# MCU2.net
KiCad netlist of a schematic drawn in Altium Designer
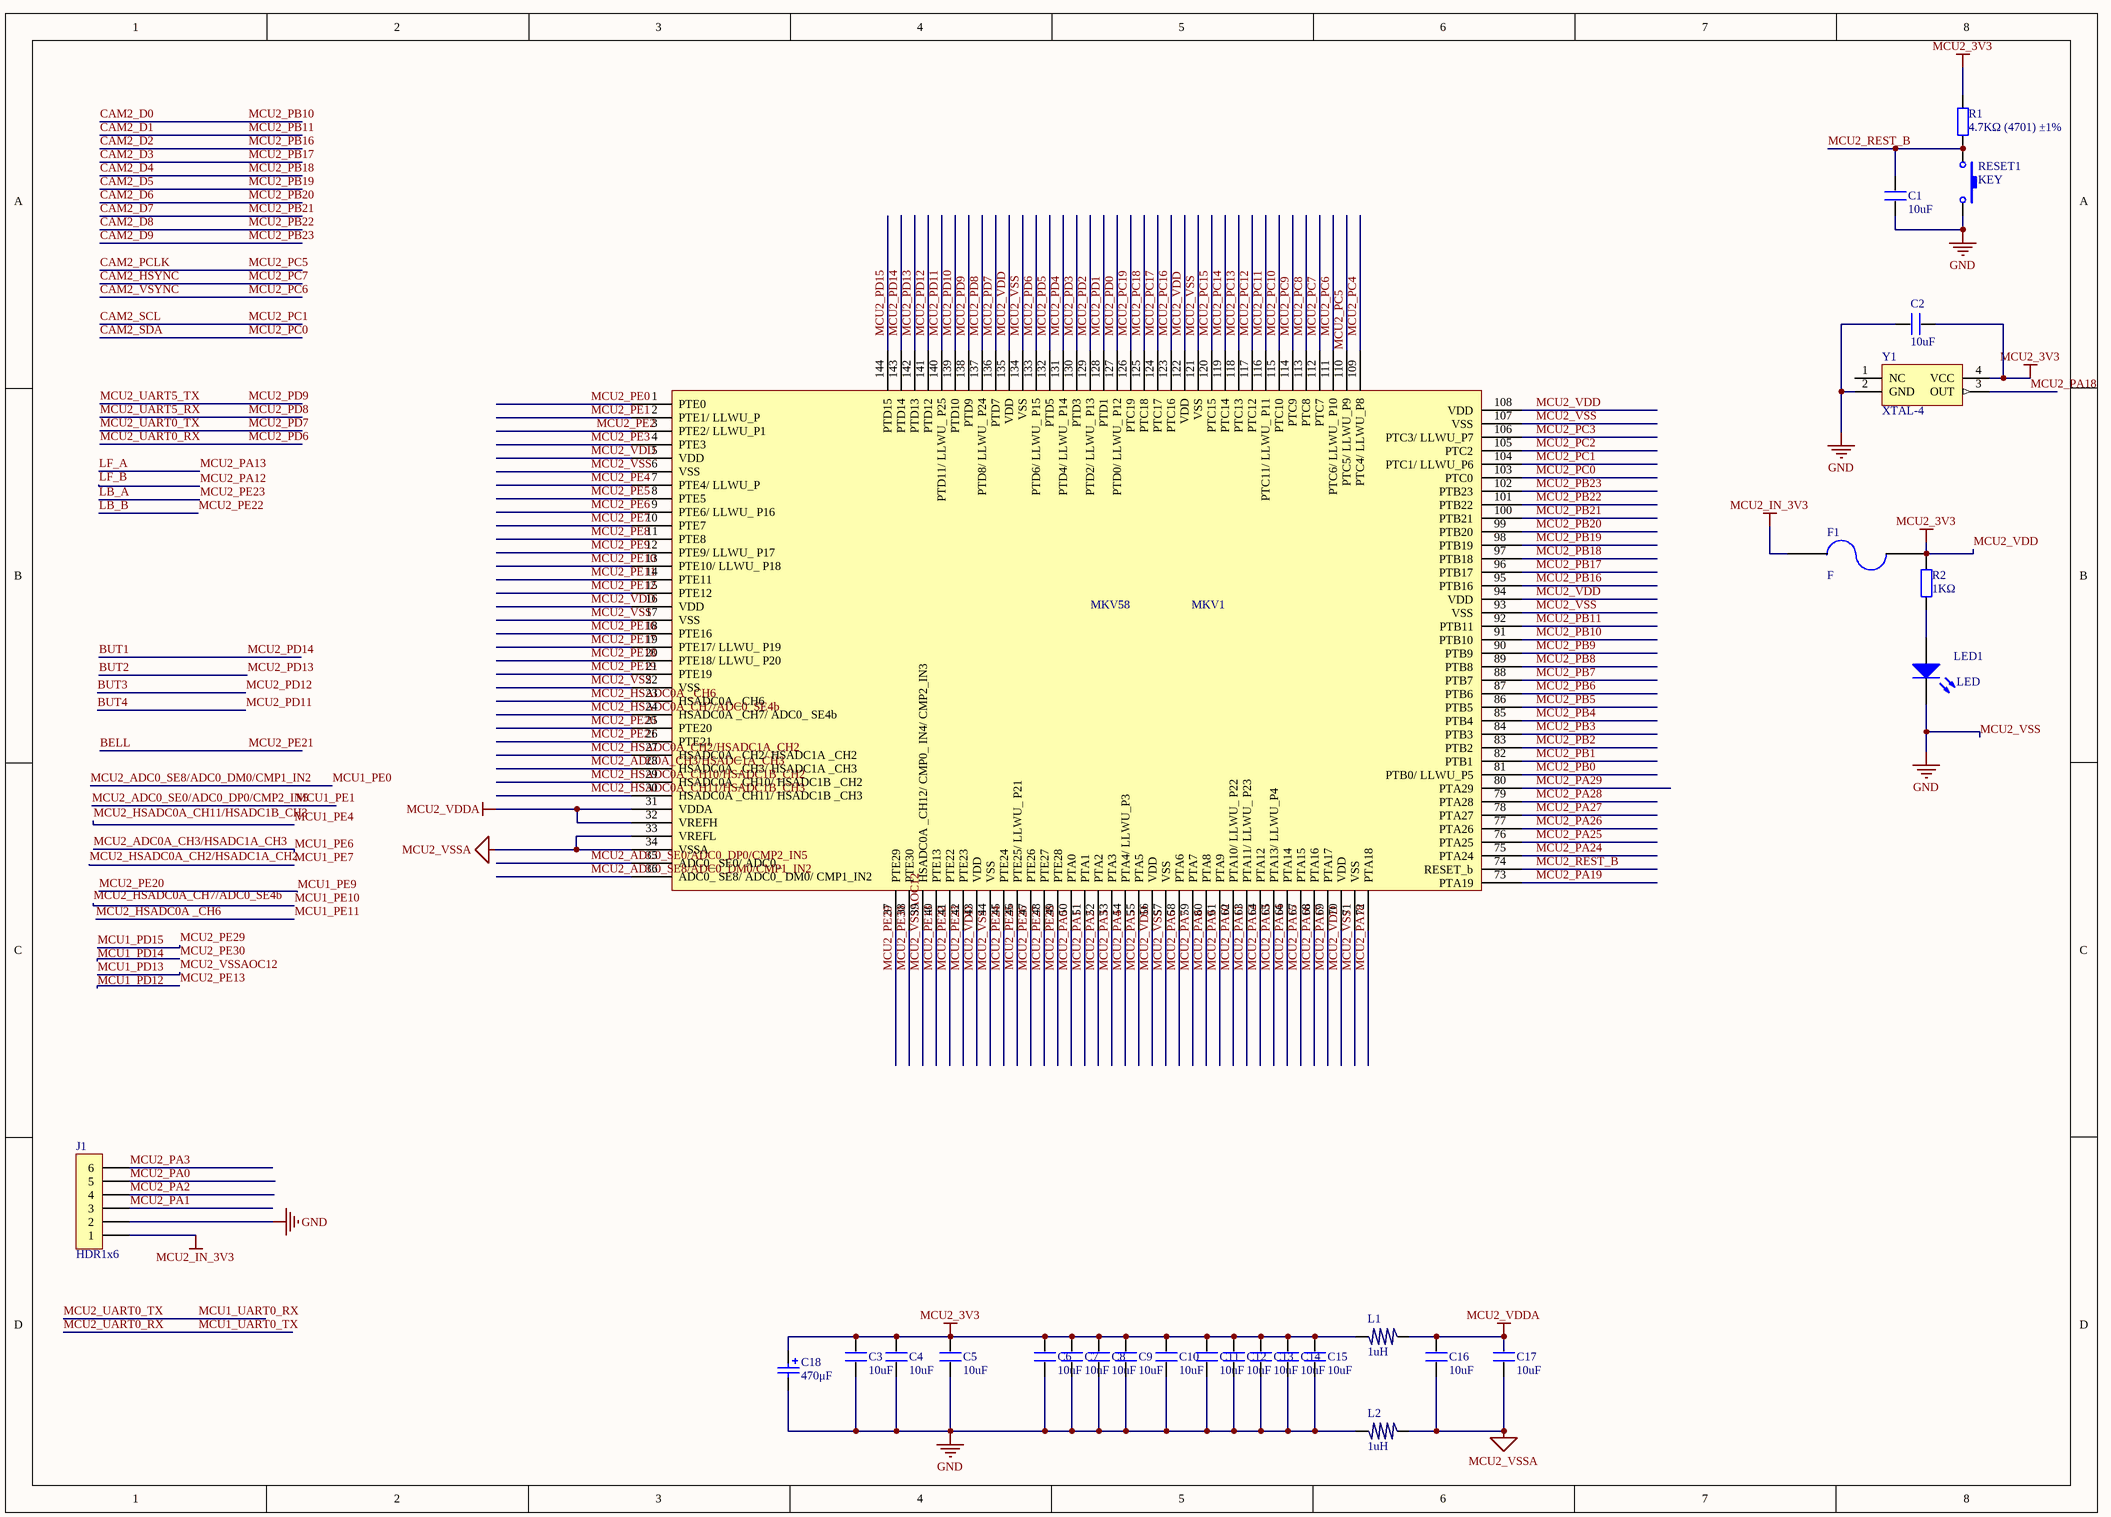
[diagram p0: MCU2.SchDoc]

(export (version "E")
  (design (tool "Eeschema 10.0.6"))
  (components
    (comp (ref "C1") (value "10uF") (footprint "0805_C") (libsource (lib "MyLib") (part "C")))
    (comp (ref "C2") (value "10uF") (footprint "0805_C") (libsource (lib "MyLib") (part "C")))
    (comp (ref "C3") (value "10uF") (footprint "0805_C") (libsource (lib "MyLib") (part "C")))
    (comp (ref "C4") (value "10uF") (footprint "0805_C") (libsource (lib "MyLib") (part "C")))
    (comp (ref "C5") (value "10uF") (footprint "0805_C") (libsource (lib "MyLib") (part "C")))
    (comp (ref "C6") (value "10uF") (footprint "0805_C") (libsource (lib "MyLib") (part "C")))
    (comp (ref "C7") (value "10uF") (footprint "0805_C") (libsource (lib "MyLib") (part "C")))
    (comp (ref "C8") (value "10uF") (footprint "0805_C") (libsource (lib "MyLib") (part "C")))
    (comp (ref "C9") (value "10uF") (footprint "0805_C") (libsource (lib "MyLib") (part "C")))
    (comp (ref "C10") (value "10uF") (footprint "0805_C") (libsource (lib "MyLib") (part "C")))
    (comp (ref "C11") (value "10uF") (footprint "0805_C") (libsource (lib "MyLib") (part "C")))
    (comp (ref "C12") (value "10uF") (footprint "0805_C") (libsource (lib "MyLib") (part "C")))
    (comp (ref "C13") (value "10uF") (footprint "0805_C") (libsource (lib "MyLib") (part "C")))
    (comp (ref "C14") (value "10uF") (footprint "0805_C") (libsource (lib "MyLib") (part "C")))
    (comp (ref "C15") (value "10uF") (footprint "0805_C") (libsource (lib "MyLib") (part "C")))
    (comp (ref "C16") (value "10uF") (footprint "0805_C") (libsource (lib "MyLib") (part "C")))
    (comp (ref "C17") (value "10uF") (footprint "0805_C") (libsource (lib "MyLib") (part "C")))
    (comp (ref "C18")
      (value "470μF")
      (footprint "CASE C6032")
      (fields (field (name "ALTIUM_UNNAMED_1") "470μF"))
      (libsource (lib "MyLib") (part "Cap(Ta)"))
    )
    (comp (ref "F1") (value "F") (footprint "0805_R") (libsource (lib "MKV58") (part "F")))
    (comp (ref "J1")
      (value "HDR1x6")
      (footprint "PIN-6-2.54-1.0")
      (description "Connector")
      (libsource (lib "MyLib") (part "HDR1x6"))
    )
    (comp (ref "L1") (value "1uH") (footprint "0805") (libsource (lib "MyLib") (part "L")))
    (comp (ref "L2") (value "1uH") (footprint "0805") (libsource (lib "MyLib") (part "L")))
    (comp (ref "LED1") (value "LED") (footprint "LED(0805)") (libsource (lib "MyLib") (part "LED(0805)")))
    (comp (ref "MKV1") (value "MKV58") (footprint "LQFP144") (libsource (lib "MyLib") (part "MKV58")))
    (comp (ref "R1")
      (value "4.7KΩ (4701) ±1%")
      (footprint "0805_R")
      (description "贴片电阻")
      (libsource (lib "MyLib") (part "0805 4.7KΩ (4701) 1%"))
    )
    (comp (ref "R2")
      (value "1KΩ")
      (footprint "0805_R")
      (description "贴片电阻")
      (libsource (lib "MyLib") (part "0805 1.5KΩ (1501) 1%"))
    )
    (comp (ref "RESET1") (value "KEY") (footprint "Key_PB") (libsource (lib "MyLib") (part "Key_1")))
    (comp (ref "Y1")
      (value "XTAL-4")
      (footprint "XTAL-5.0X3.2")
      (description "Oscillator")
      (libsource (lib "MyLib") (part "XTAL-4"))
    )
  )
  (nets
    (net (code "2") (name "/BELL") (class "Default")
      (node (ref "MKV1") (pin "26") (pinfunction "PTE21_26") (pintype "passive"))
    )
    (net (code "3") (name "/BUT1") (class "Default")
      (node (ref "MKV1") (pin "143") (pinfunction "PTD14_143") (pintype "passive"))
    )
    (net (code "4") (name "/BUT2") (class "Default")
      (node (ref "MKV1") (pin "142") (pinfunction "PTD13_142") (pintype "passive"))
    )
    (net (code "5") (name "/BUT3") (class "Default")
      (node (ref "MKV1") (pin "141") (pinfunction "PTD12_141") (pintype "passive"))
    )
    (net (code "6") (name "/BUT4") (class "Default")
      (node (ref "MKV1") (pin "140") (pinfunction "PTD11/_LLWU__P25_140") (pintype "passive"))
    )
    (net (code "7") (name "/CAM2_D0") (class "Default")
      (node (ref "MKV1") (pin "91") (pinfunction "PTB10_91") (pintype "passive"))
    )
    (net (code "8") (name "/CAM2_D1") (class "Default")
      (node (ref "MKV1") (pin "92") (pinfunction "PTB11_92") (pintype "passive"))
    )
    (net (code "9") (name "/CAM2_D2") (class "Default")
      (node (ref "MKV1") (pin "95") (pinfunction "PTB16_95") (pintype "passive"))
    )
    (net (code "10") (name "/CAM2_D3") (class "Default")
      (node (ref "MKV1") (pin "96") (pinfunction "PTB17_96") (pintype "passive"))
    )
    (net (code "11") (name "/CAM2_D4") (class "Default")
      (node (ref "MKV1") (pin "97") (pinfunction "PTB18_97") (pintype "passive"))
    )
    (net (code "12") (name "/CAM2_D5") (class "Default")
      (node (ref "MKV1") (pin "98") (pinfunction "PTB19_98") (pintype "passive"))
    )
    (net (code "13") (name "/CAM2_D6") (class "Default")
      (node (ref "MKV1") (pin "99") (pinfunction "PTB20_99") (pintype "passive"))
    )
    (net (code "14") (name "/CAM2_D7") (class "Default")
      (node (ref "MKV1") (pin "100") (pinfunction "PTB21_100") (pintype "passive"))
    )
    (net (code "15") (name "/CAM2_D8") (class "Default")
      (node (ref "MKV1") (pin "101") (pinfunction "PTB22_101") (pintype "passive"))
    )
    (net (code "16") (name "/CAM2_D9") (class "Default")
      (node (ref "MKV1") (pin "102") (pinfunction "PTB23_102") (pintype "passive"))
    )
    (net (code "17") (name "/CAM2_HSYNC") (class "Default")
      (node (ref "MKV1") (pin "112") (pinfunction "PTC7_112") (pintype "passive"))
    )
    (net (code "18") (name "/CAM2_PCLK") (class "Default")
      (node (ref "MKV1") (pin "110") (pinfunction "PTC5/_LLWU_P9_110") (pintype "passive"))
    )
    (net (code "19") (name "/CAM2_SCL") (class "Default")
      (node (ref "MKV1") (pin "104") (pinfunction "PTC1/_LLWU_P6_104") (pintype "passive"))
    )
    (net (code "20") (name "/CAM2_SDA") (class "Default")
      (node (ref "MKV1") (pin "103") (pinfunction "PTC0_103") (pintype "passive"))
    )
    (net (code "21") (name "/CAM2_VSYNC") (class "Default")
      (node (ref "MKV1") (pin "111") (pinfunction "PTC6/_LLWU__P10_111") (pintype "passive"))
    )
    (net (code "22") (name "/LB_A") (class "Default")
      (node (ref "MKV1") (pin "42") (pinfunction "PTE23_42") (pintype "passive"))
    )
    (net (code "23") (name "/LB_B") (class "Default")
      (node (ref "MKV1") (pin "41") (pinfunction "PTE22_41") (pintype "passive"))
    )
    (net (code "24") (name "/LF_A") (class "Default")
      (node (ref "MKV1") (pin "65") (pinfunction "PTA13/_LLWU_P4_65") (pintype "passive"))
    )
    (net (code "25") (name "/LF_B") (class "Default")
      (node (ref "MKV1") (pin "64") (pinfunction "PTA12_64") (pintype "passive"))
    )
    (net (code "26") (name "/MCU1_PD12") (class "Default")
      (node (ref "MKV1") (pin "40") (pinfunction "PTE13_40") (pintype "passive"))
    )
    (net (code "27") (name "/MCU1_PD13") (class "Default")
      (node (ref "MKV1") (pin "39") (pinfunction "HSADC0A__CH12/_CMP0__IN4/_CMP2_IN3_39") (pintype "passive"))
    )
    (net (code "28") (name "/MCU1_PD14") (class "Default")
      (node (ref "MKV1") (pin "38") (pinfunction "PTE30_38") (pintype "passive"))
    )
    (net (code "29") (name "/MCU1_PD15") (class "Default")
      (node (ref "MKV1") (pin "37") (pinfunction "PTE29_37") (pintype "passive"))
    )
    (net (code "30") (name "/MCU1_PE0") (class "Default")
      (node (ref "MKV1") (pin "36") (pinfunction "ADC0__SE8/_ADC0__DM0/_CMP1_IN2_36") (pintype "passive"))
    )
    (net (code "31") (name "/MCU1_PE1") (class "Default")
      (node (ref "MKV1") (pin "35") (pinfunction "ADC0__SE0/_ADC0__35") (pintype "passive"))
    )
    (net (code "32") (name "/MCU1_PE4") (class "Default")
      (node (ref "MKV1") (pin "30") (pinfunction "HSADC0A__CH11/_HSADC1B__CH3_30") (pintype "passive"))
    )
    (net (code "33") (name "/MCU1_PE6") (class "Default")
      (node (ref "MKV1") (pin "28") (pinfunction "HSADC0A__CH3/_HSADC1A__CH3_28") (pintype "passive"))
    )
    (net (code "34") (name "/MCU1_PE7") (class "Default")
      (node (ref "MKV1") (pin "27") (pinfunction "HSADC0A__CH2/_HSADC1A__CH2_27") (pintype "passive"))
    )
    (net (code "35") (name "/MCU1_PE9") (class "Default")
      (node (ref "MKV1") (pin "25") (pinfunction "PTE20_25") (pintype "passive"))
    )
    (net (code "36") (name "/MCU1_PE10") (class "Default")
      (node (ref "MKV1") (pin "24") (pinfunction "HSADC0A__CH7/_ADC0__SE4b_24") (pintype "passive"))
    )
    (net (code "37") (name "/MCU1_PE11") (class "Default")
      (node (ref "MKV1") (pin "23") (pinfunction "HSADC0A__CH6_23") (pintype "passive"))
    )
    (net (code "38") (name "/MCU1_UART0_RX") (class "Default")
      (node (ref "MKV1") (pin "136") (pinfunction "PTD7_136") (pintype "passive"))
    )
    (net (code "39") (name "/MCU1_UART0_TX") (class "Default")
      (node (ref "MKV1") (pin "133") (pinfunction "PTD6/_LLWU__P15_133") (pintype "passive"))
    )
    (net (code "40") (name "/MCU2_HSADC0A_CH10{slash}HSADC1B_CH2") (class "Default")
      (node (ref "MKV1") (pin "29") (pinfunction "HSADC0A__CH10/_HSADC1B__CH2_29") (pintype "passive"))
    )
    (net (code "41") (name "/MCU2_PA0") (class "Default")
      (node (ref "J1") (pin "5") (pinfunction "5_5") (pintype "passive"))
      (node (ref "MKV1") (pin "50") (pinfunction "PTA0_50") (pintype "passive"))
    )
    (net (code "42") (name "/MCU2_PA1") (class "Default")
      (node (ref "J1") (pin "3") (pinfunction "3_3") (pintype "passive"))
      (node (ref "MKV1") (pin "51") (pinfunction "PTA1_51") (pintype "passive"))
    )
    (net (code "43") (name "/MCU2_PA2") (class "Default")
      (node (ref "J1") (pin "4") (pinfunction "4_4") (pintype "passive"))
      (node (ref "MKV1") (pin "52") (pinfunction "PTA2_52") (pintype "passive"))
    )
    (net (code "44") (name "/MCU2_PA3") (class "Default")
      (node (ref "J1") (pin "6") (pinfunction "6_6") (pintype "passive"))
      (node (ref "MKV1") (pin "53") (pinfunction "PTA3_53") (pintype "passive"))
    )
    (net (code "45") (name "/MCU2_PA4") (class "Default")
      (node (ref "MKV1") (pin "54") (pinfunction "PTA4/_LLWU_P3_54") (pintype "passive"))
    )
    (net (code "46") (name "/MCU2_PA5") (class "Default")
      (node (ref "MKV1") (pin "55") (pinfunction "PTA5_55") (pintype "passive"))
    )
    (net (code "47") (name "/MCU2_PA6") (class "Default")
      (node (ref "MKV1") (pin "58") (pinfunction "PTA6_58") (pintype "passive"))
    )
    (net (code "48") (name "/MCU2_PA7") (class "Default")
      (node (ref "MKV1") (pin "59") (pinfunction "PTA7_59") (pintype "passive"))
    )
    (net (code "49") (name "/MCU2_PA8") (class "Default")
      (node (ref "MKV1") (pin "60") (pinfunction "PTA8_60") (pintype "passive"))
    )
    (net (code "50") (name "/MCU2_PA9") (class "Default")
      (node (ref "MKV1") (pin "61") (pinfunction "PTA9_61") (pintype "passive"))
    )
    (net (code "51") (name "/MCU2_PA10") (class "Default")
      (node (ref "MKV1") (pin "62") (pinfunction "PTA10/_LLWU__P22_62") (pintype "passive"))
    )
    (net (code "52") (name "/MCU2_PA11") (class "Default")
      (node (ref "MKV1") (pin "63") (pinfunction "PTA11/_LLWU__P23_63") (pintype "passive"))
    )
    (net (code "53") (name "/MCU2_PA14") (class "Default")
      (node (ref "MKV1") (pin "66") (pinfunction "PTA14_66") (pintype "passive"))
    )
    (net (code "54") (name "/MCU2_PA15") (class "Default")
      (node (ref "MKV1") (pin "67") (pinfunction "PTA15_67") (pintype "passive"))
    )
    (net (code "55") (name "/MCU2_PA16") (class "Default")
      (node (ref "MKV1") (pin "68") (pinfunction "PTA16_68") (pintype "passive"))
    )
    (net (code "56") (name "/MCU2_PA17") (class "Default")
      (node (ref "MKV1") (pin "69") (pinfunction "PTA17_69") (pintype "passive"))
    )
    (net (code "57") (name "/MCU2_PA18") (class "Default")
      (node (ref "MKV1") (pin "72") (pinfunction "PTA18_72") (pintype "passive"))
      (node (ref "Y1") (pin "3") (pinfunction "OUT_3") (pintype "output"))
    )
    (net (code "58") (name "/MCU2_PA19") (class "Default")
      (node (ref "MKV1") (pin "73") (pinfunction "PTA19_73") (pintype "passive"))
    )
    (net (code "59") (name "/MCU2_PA24") (class "Default")
      (node (ref "MKV1") (pin "75") (pinfunction "PTA24_75") (pintype "passive"))
    )
    (net (code "60") (name "/MCU2_PA25") (class "Default")
      (node (ref "MKV1") (pin "76") (pinfunction "PTA25_76") (pintype "passive"))
    )
    (net (code "61") (name "/MCU2_PA26") (class "Default")
      (node (ref "MKV1") (pin "77") (pinfunction "PTA26_77") (pintype "passive"))
    )
    (net (code "62") (name "/MCU2_PA27") (class "Default")
      (node (ref "MKV1") (pin "78") (pinfunction "PTA27_78") (pintype "passive"))
    )
    (net (code "63") (name "/MCU2_PA28") (class "Default")
      (node (ref "MKV1") (pin "79") (pinfunction "PTA28_79") (pintype "passive"))
    )
    (net (code "64") (name "/MCU2_PA29") (class "Default")
      (node (ref "MKV1") (pin "80") (pinfunction "PTA29_80") (pintype "passive"))
    )
    (net (code "65") (name "/MCU2_PB0") (class "Default")
      (node (ref "MKV1") (pin "81") (pinfunction "PTB0/_LLWU_P5_81") (pintype "passive"))
    )
    (net (code "66") (name "/MCU2_PB1") (class "Default")
      (node (ref "MKV1") (pin "82") (pinfunction "PTB1_82") (pintype "passive"))
    )
    (net (code "67") (name "/MCU2_PB2") (class "Default")
      (node (ref "MKV1") (pin "83") (pinfunction "PTB2_83") (pintype "passive"))
    )
    (net (code "68") (name "/MCU2_PB3") (class "Default")
      (node (ref "MKV1") (pin "84") (pinfunction "PTB3_84") (pintype "passive"))
    )
    (net (code "69") (name "/MCU2_PB4") (class "Default")
      (node (ref "MKV1") (pin "85") (pinfunction "PTB4_85") (pintype "passive"))
    )
    (net (code "70") (name "/MCU2_PB5") (class "Default")
      (node (ref "MKV1") (pin "86") (pinfunction "PTB5_86") (pintype "passive"))
    )
    (net (code "71") (name "/MCU2_PB6") (class "Default")
      (node (ref "MKV1") (pin "87") (pinfunction "PTB6_87") (pintype "passive"))
    )
    (net (code "72") (name "/MCU2_PB7") (class "Default")
      (node (ref "MKV1") (pin "88") (pinfunction "PTB7_88") (pintype "passive"))
    )
    (net (code "73") (name "/MCU2_PB8") (class "Default")
      (node (ref "MKV1") (pin "89") (pinfunction "PTB8_89") (pintype "passive"))
    )
    (net (code "74") (name "/MCU2_PB9") (class "Default")
      (node (ref "MKV1") (pin "90") (pinfunction "PTB9_90") (pintype "passive"))
    )
    (net (code "75") (name "/MCU2_PC2") (class "Default")
      (node (ref "MKV1") (pin "105") (pinfunction "PTC2_105") (pintype "passive"))
    )
    (net (code "76") (name "/MCU2_PC3") (class "Default")
      (node (ref "MKV1") (pin "106") (pinfunction "PTC3/_LLWU_P7_106") (pintype "passive"))
    )
    (net (code "77") (name "/MCU2_PC4") (class "Default")
      (node (ref "MKV1") (pin "109") (pinfunction "PTC4/_LLWU_P8_109") (pintype "passive"))
    )
    (net (code "78") (name "/MCU2_PC8") (class "Default")
      (node (ref "MKV1") (pin "113") (pinfunction "PTC8_113") (pintype "passive"))
    )
    (net (code "79") (name "/MCU2_PC9") (class "Default")
      (node (ref "MKV1") (pin "114") (pinfunction "PTC9_114") (pintype "passive"))
    )
    (net (code "80") (name "/MCU2_PC10") (class "Default")
      (node (ref "MKV1") (pin "115") (pinfunction "PTC10_115") (pintype "passive"))
    )
    (net (code "81") (name "/MCU2_PC11") (class "Default")
      (node (ref "MKV1") (pin "116") (pinfunction "PTC11/_LLWU__P11_116") (pintype "passive"))
    )
    (net (code "82") (name "/MCU2_PC12") (class "Default")
      (node (ref "MKV1") (pin "117") (pinfunction "PTC12_117") (pintype "passive"))
    )
    (net (code "83") (name "/MCU2_PC13") (class "Default")
      (node (ref "MKV1") (pin "118") (pinfunction "PTC13_118") (pintype "passive"))
    )
    (net (code "84") (name "/MCU2_PC14") (class "Default")
      (node (ref "MKV1") (pin "119") (pinfunction "PTC14_119") (pintype "passive"))
    )
    (net (code "85") (name "/MCU2_PC15") (class "Default")
      (node (ref "MKV1") (pin "120") (pinfunction "PTC15_120") (pintype "passive"))
    )
    (net (code "86") (name "/MCU2_PC16") (class "Default")
      (node (ref "MKV1") (pin "123") (pinfunction "PTC16_123") (pintype "passive"))
    )
    (net (code "87") (name "/MCU2_PC17") (class "Default")
      (node (ref "MKV1") (pin "124") (pinfunction "PTC17_124") (pintype "passive"))
    )
    (net (code "88") (name "/MCU2_PC18") (class "Default")
      (node (ref "MKV1") (pin "125") (pinfunction "PTC18_125") (pintype "passive"))
    )
    (net (code "89") (name "/MCU2_PC19") (class "Default")
      (node (ref "MKV1") (pin "126") (pinfunction "PTC19_126") (pintype "passive"))
    )
    (net (code "90") (name "/MCU2_PD0") (class "Default")
      (node (ref "MKV1") (pin "127") (pinfunction "PTD0/_LLWU__P12_127") (pintype "passive"))
    )
    (net (code "91") (name "/MCU2_PD1") (class "Default")
      (node (ref "MKV1") (pin "128") (pinfunction "PTD1_128") (pintype "passive"))
    )
    (net (code "92") (name "/MCU2_PD2") (class "Default")
      (node (ref "MKV1") (pin "129") (pinfunction "PTD2/_LLWU__P13_129") (pintype "passive"))
    )
    (net (code "93") (name "/MCU2_PD3") (class "Default")
      (node (ref "MKV1") (pin "130") (pinfunction "PTD3_130") (pintype "passive"))
    )
    (net (code "94") (name "/MCU2_PD4") (class "Default")
      (node (ref "MKV1") (pin "131") (pinfunction "PTD4/_LLWU__P14_131") (pintype "passive"))
    )
    (net (code "95") (name "/MCU2_PD5") (class "Default")
      (node (ref "MKV1") (pin "132") (pinfunction "PTD5_132") (pintype "passive"))
    )
    (net (code "96") (name "/MCU2_PD8") (class "Default")
      (node (ref "MKV1") (pin "137") (pinfunction "PTD8/_LLWU__P24_137") (pintype "passive"))
    )
    (net (code "97") (name "/MCU2_PD9") (class "Default")
      (node (ref "MKV1") (pin "138") (pinfunction "PTD9_138") (pintype "passive"))
    )
    (net (code "98") (name "/MCU2_PD10") (class "Default")
      (node (ref "MKV1") (pin "139") (pinfunction "PTD10_139") (pintype "passive"))
    )
    (net (code "99") (name "/MCU2_PD15") (class "Default")
      (node (ref "MKV1") (pin "144") (pinfunction "PTD15_144") (pintype "passive"))
    )
    (net (code "100") (name "/MCU2_PE0") (class "Default")
      (node (ref "MKV1") (pin "1") (pinfunction "PTE0_1") (pintype "passive"))
    )
    (net (code "101") (name "/MCU2_PE1") (class "Default")
      (node (ref "MKV1") (pin "2") (pinfunction "PTE1/_LLWU_P_2") (pintype "passive"))
    )
    (net (code "102") (name "/MCU2_PE2") (class "Default")
      (node (ref "MKV1") (pin "3") (pinfunction "PTE2/_LLWU_P1_3") (pintype "passive"))
    )
    (net (code "103") (name "/MCU2_PE3") (class "Default")
      (node (ref "MKV1") (pin "4") (pinfunction "PTE3_4") (pintype "passive"))
    )
    (net (code "104") (name "/MCU2_PE4") (class "Default")
      (node (ref "MKV1") (pin "7") (pinfunction "PTE4/_LLWU_P_7") (pintype "passive"))
    )
    (net (code "105") (name "/MCU2_PE5") (class "Default")
      (node (ref "MKV1") (pin "8") (pinfunction "PTE5_8") (pintype "passive"))
    )
    (net (code "106") (name "/MCU2_PE6") (class "Default")
      (node (ref "MKV1") (pin "9") (pinfunction "PTE6/_LLWU__P16_9") (pintype "passive"))
    )
    (net (code "107") (name "/MCU2_PE7") (class "Default")
      (node (ref "MKV1") (pin "10") (pinfunction "PTE7_10") (pintype "passive"))
    )
    (net (code "108") (name "/MCU2_PE8") (class "Default")
      (node (ref "MKV1") (pin "11") (pinfunction "PTE8_11") (pintype "passive"))
    )
    (net (code "109") (name "/MCU2_PE9") (class "Default")
      (node (ref "MKV1") (pin "12") (pinfunction "PTE9/_LLWU__P17_12") (pintype "passive"))
    )
    (net (code "110") (name "/MCU2_PE10") (class "Default")
      (node (ref "MKV1") (pin "13") (pinfunction "PTE10/_LLWU__P18_13") (pintype "passive"))
    )
    (net (code "111") (name "/MCU2_PE11") (class "Default")
      (node (ref "MKV1") (pin "14") (pinfunction "PTE11_14") (pintype "passive"))
    )
    (net (code "112") (name "/MCU2_PE12") (class "Default")
      (node (ref "MKV1") (pin "15") (pinfunction "PTE12_15") (pintype "passive"))
    )
    (net (code "113") (name "/MCU2_PE16") (class "Default")
      (node (ref "MKV1") (pin "18") (pinfunction "PTE16_18") (pintype "passive"))
    )
    (net (code "114") (name "/MCU2_PE17") (class "Default")
      (node (ref "MKV1") (pin "19") (pinfunction "PTE17/_LLWU__P19_19") (pintype "passive"))
    )
    (net (code "115") (name "/MCU2_PE18") (class "Default")
      (node (ref "MKV1") (pin "20") (pinfunction "PTE18/_LLWU__P20_20") (pintype "passive"))
    )
    (net (code "116") (name "/MCU2_PE19") (class "Default")
      (node (ref "MKV1") (pin "21") (pinfunction "PTE19_21") (pintype "passive"))
    )
    (net (code "117") (name "/MCU2_PE24") (class "Default")
      (node (ref "MKV1") (pin "45") (pinfunction "PTE24_45") (pintype "passive"))
    )
    (net (code "118") (name "/MCU2_PE25") (class "Default")
      (node (ref "MKV1") (pin "46") (pinfunction "PTE25/_LLWU__P21_46") (pintype "passive"))
    )
    (net (code "119") (name "/MCU2_PE26") (class "Default")
      (node (ref "MKV1") (pin "47") (pinfunction "PTE26_47") (pintype "passive"))
    )
    (net (code "120") (name "/MCU2_PE27") (class "Default")
      (node (ref "MKV1") (pin "48") (pinfunction "PTE27_48") (pintype "passive"))
    )
    (net (code "121") (name "/MCU2_PE28") (class "Default")
      (node (ref "MKV1") (pin "49") (pinfunction "PTE28_49") (pintype "passive"))
    )
    (net (code "122") (name "/MCU2_REST_B") (class "Default")
      (node (ref "C1") (pin "2") (pintype "passive"))
      (node (ref "MKV1") (pin "74") (pinfunction "RESET_b_74") (pintype "passive"))
      (node (ref "R1") (pin "1") (pinfunction "1_1") (pintype "passive"))
      (node (ref "RESET1") (pin "1") (pinfunction "1_1") (pintype "passive"))
    )
    (net (code "123") (name "GND") (class "Default")
      (node (ref "C1") (pin "1") (pintype "passive"))
      (node (ref "C10") (pin "1") (pintype "passive"))
      (node (ref "C11") (pin "1") (pintype "passive"))
      (node (ref "C12") (pin "1") (pintype "passive"))
      (node (ref "C13") (pin "1") (pintype "passive"))
      (node (ref "C14") (pin "1") (pintype "passive"))
      (node (ref "C15") (pin "1") (pintype "passive"))
      (node (ref "C18") (pin "2") (pinfunction "2_2") (pintype "passive"))
      (node (ref "C2") (pin "1") (pintype "passive"))
      (node (ref "C3") (pin "1") (pintype "passive"))
      (node (ref "C4") (pin "1") (pintype "passive"))
      (node (ref "C5") (pin "1") (pintype "passive"))
      (node (ref "C6") (pin "1") (pintype "passive"))
      (node (ref "C7") (pin "1") (pintype "passive"))
      (node (ref "C8") (pin "1") (pintype "passive"))
      (node (ref "C9") (pin "1") (pintype "passive"))
      (node (ref "J1") (pin "2") (pinfunction "2_2") (pintype "passive"))
      (node (ref "L2") (pin "2") (pintype "passive"))
      (node (ref "LED1") (pin "2") (pinfunction "K_2") (pintype "passive"))
      (node (ref "MKV1") (pin "107") (pinfunction "VSS_107") (pintype "passive"))
      (node (ref "MKV1") (pin "121") (pinfunction "VSS_121") (pintype "passive"))
      (node (ref "MKV1") (pin "134") (pinfunction "VSS_134") (pintype "passive"))
      (node (ref "MKV1") (pin "17") (pinfunction "VSS_17") (pintype "passive"))
      (node (ref "MKV1") (pin "22") (pinfunction "VSS_22") (pintype "passive"))
      (node (ref "MKV1") (pin "44") (pinfunction "VSS_44") (pintype "passive"))
      (node (ref "MKV1") (pin "57") (pinfunction "VSS_57") (pintype "passive"))
      (node (ref "MKV1") (pin "6") (pinfunction "VSS_6") (pintype "passive"))
      (node (ref "MKV1") (pin "71") (pinfunction "VSS_71") (pintype "passive"))
      (node (ref "MKV1") (pin "93") (pinfunction "VSS_93") (pintype "passive"))
      (node (ref "RESET1") (pin "2") (pinfunction "2_2") (pintype "passive"))
      (node (ref "Y1") (pin "2") (pinfunction "GND_2") (pintype "power_in"))
    )
    (net (code "124") (name "MCU2_3V3") (class "Default")
      (node (ref "C10") (pin "2") (pintype "passive"))
      (node (ref "C11") (pin "2") (pintype "passive"))
      (node (ref "C12") (pin "2") (pintype "passive"))
      (node (ref "C13") (pin "2") (pintype "passive"))
      (node (ref "C14") (pin "2") (pintype "passive"))
      (node (ref "C15") (pin "2") (pintype "passive"))
      (node (ref "C18") (pin "1") (pinfunction "1_1") (pintype "passive"))
      (node (ref "C2") (pin "2") (pintype "passive"))
      (node (ref "C3") (pin "2") (pintype "passive"))
      (node (ref "C4") (pin "2") (pintype "passive"))
      (node (ref "C5") (pin "2") (pintype "passive"))
      (node (ref "C6") (pin "2") (pintype "passive"))
      (node (ref "C7") (pin "2") (pintype "passive"))
      (node (ref "C8") (pin "2") (pintype "passive"))
      (node (ref "C9") (pin "2") (pintype "passive"))
      (node (ref "F1") (pin "2") (pinfunction "1_2") (pintype "passive"))
      (node (ref "L1") (pin "2") (pintype "passive"))
      (node (ref "MKV1") (pin "108") (pinfunction "VDD_108") (pintype "passive"))
      (node (ref "MKV1") (pin "122") (pinfunction "VDD_122") (pintype "passive"))
      (node (ref "MKV1") (pin "135") (pinfunction "VDD_135") (pintype "passive"))
      (node (ref "MKV1") (pin "16") (pinfunction "VDD_16") (pintype "passive"))
      (node (ref "MKV1") (pin "43") (pinfunction "VDD_43") (pintype "passive"))
      (node (ref "MKV1") (pin "5") (pinfunction "VDD_5") (pintype "passive"))
      (node (ref "MKV1") (pin "56") (pinfunction "VDD_56") (pintype "passive"))
      (node (ref "MKV1") (pin "70") (pinfunction "VDD_70") (pintype "passive"))
      (node (ref "MKV1") (pin "94") (pinfunction "VDD_94") (pintype "passive"))
      (node (ref "R1") (pin "2") (pinfunction "2_2") (pintype "passive"))
      (node (ref "R2") (pin "2") (pinfunction "2_2") (pintype "passive"))
      (node (ref "Y1") (pin "4") (pinfunction "VCC_4") (pintype "power_in"))
    )
    (net (code "125") (name "MCU2_IN_3V3") (class "Default")
      (node (ref "F1") (pin "1") (pinfunction "0_1") (pintype "passive"))
      (node (ref "J1") (pin "1") (pinfunction "1_1") (pintype "passive"))
    )
    (net (code "126") (name "MCU2_VDDA") (class "Default")
      (node (ref "C16") (pin "2") (pintype "passive"))
      (node (ref "C17") (pin "2") (pintype "passive"))
      (node (ref "L1") (pin "1") (pintype "passive"))
      (node (ref "MKV1") (pin "31") (pinfunction "VDDA_31") (pintype "passive"))
      (node (ref "MKV1") (pin "32") (pinfunction "VREFH_32") (pintype "passive"))
    )
    (net (code "127") (name "MCU2_VSSA") (class "Default")
      (node (ref "C16") (pin "1") (pintype "passive"))
      (node (ref "C17") (pin "1") (pintype "passive"))
      (node (ref "L2") (pin "1") (pintype "passive"))
      (node (ref "MKV1") (pin "33") (pinfunction "VREFL_33") (pintype "passive"))
      (node (ref "MKV1") (pin "34") (pinfunction "VSSA_34") (pintype "passive"))
    )
    (net (code "128") (name "Net-(LED1-A)") (class "Default")
      (node (ref "LED1") (pin "1") (pinfunction "A_1") (pintype "passive"))
      (node (ref "R2") (pin "1") (pinfunction "1_1") (pintype "passive"))
    )
    (net (code "129") (name "unconnected-(Y1-NC-Pad1)") (class "Default")
      (node (ref "Y1") (pin "1") (pinfunction "NC_1") (pintype "passive"))
    )
  )
)
